# esp.net
KiCad netlist of a schematic drawn in EAGLE
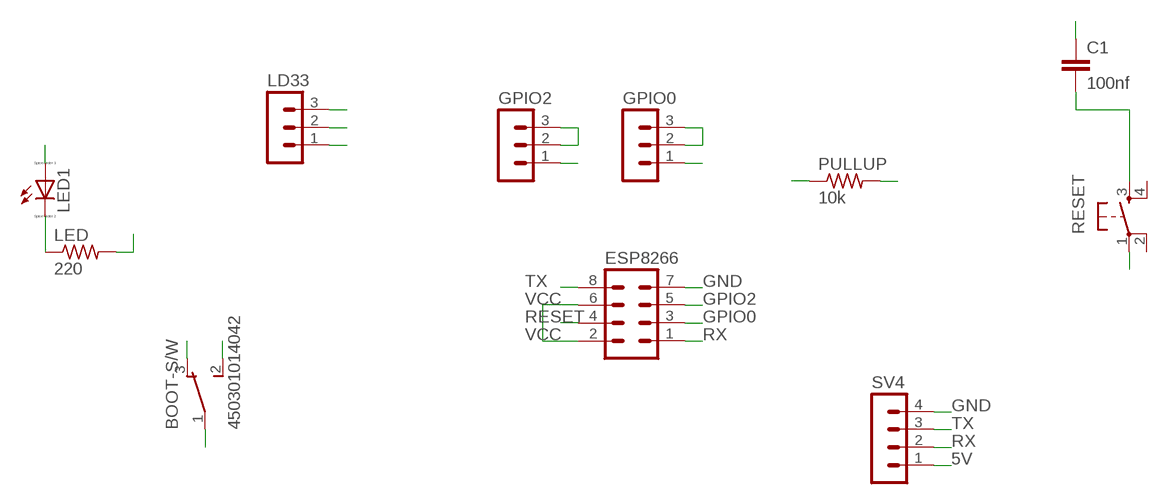
[diagram p0: schematic, sheet 1]

(export (version "E")
  (design (tool "Eeschema 10.0.6"))
  (components
    (comp (ref "BOOT-S/W")
      (value "450301014042")
      (footprint "eagle-import:450301014042")
      (libsource (lib "eagle-import") (part "450301014042"))
    )
    (comp (ref "C1")
      (value "100nf")
      (footprint "eagle-import:C025-024X044")
      (libsource (lib "eagle-import") (part "C-EU025-024X044"))
    )
    (comp (ref "ESP8266")
      (value "MA04-2")
      (footprint "eagle-import:MA04-2")
      (libsource (lib "eagle-import") (part "MA04-2"))
    )
    (comp (ref "GPIO0")
      (value "MA03-1")
      (footprint "eagle-import:MA03-1")
      (libsource (lib "eagle-import") (part "MA03-1"))
    )
    (comp (ref "GPIO2")
      (value "MA03-1")
      (footprint "eagle-import:MA03-1")
      (libsource (lib "eagle-import") (part "MA03-1"))
    )
    (comp (ref "LD33")
      (value "MA03-1")
      (footprint "eagle-import:MA03-1")
      (libsource (lib "eagle-import") (part "MA03-1"))
    )
    (comp (ref "LED")
      (value "220")
      (footprint "eagle-import:0204_5")
      (libsource (lib "eagle-import") (part "R-US_0204/5"))
    )
    (comp (ref "LED1")
      (value "LED_ELD260")
      (footprint "eagle-import:LED_LD260")
      (libsource (lib "eagle-import") (part "LED_ELD260"))
    )
    (comp (ref "PULLUP")
      (value "10k")
      (footprint "eagle-import:0204_5")
      (libsource (lib "eagle-import") (part "R-US_0204/5"))
    )
    (comp (ref "RESET")
      (value "DTS-6")
      (footprint "eagle-import:DTS-6")
      (libsource (lib "eagle-import") (part "DTS-6"))
    )
    (comp (ref "SV4")
      (value "MA04-1")
      (footprint "eagle-import:MA04-1")
      (libsource (lib "eagle-import") (part "MA04-1"))
    )
  )
  (nets
    (net (code "1") (name "/5V") (class "Default")
      (node (ref "LD33") (pin "1") (pinfunction "1_1") (pintype "passive"))
      (node (ref "SV4") (pin "1") (pinfunction "1_1") (pintype "passive"))
    )
    (net (code "2") (name "/GND") (class "Default")
      (node (ref "BOOT-S/W") (pin "3") (pinfunction "3_3") (pintype "passive"))
      (node (ref "ESP8266") (pin "7") (pinfunction "7_7") (pintype "passive"))
      (node (ref "GPIO0") (pin "1") (pinfunction "1_1") (pintype "passive"))
      (node (ref "GPIO2") (pin "1") (pinfunction "1_1") (pintype "passive"))
      (node (ref "LD33") (pin "2") (pinfunction "2_2") (pintype "passive"))
      (node (ref "LED") (pin "2") (pinfunction "2_2") (pintype "passive"))
      (node (ref "RESET") (pin "1") (pinfunction "1_1") (pintype "passive"))
      (node (ref "SV4") (pin "4") (pinfunction "4_4") (pintype "passive"))
    )
    (net (code "3") (name "/GPIO0") (class "Default")
      (node (ref "BOOT-S/W") (pin "1") (pinfunction "1_1") (pintype "passive"))
      (node (ref "ESP8266") (pin "3") (pinfunction "3_3") (pintype "passive"))
    )
    (net (code "4") (name "/GPIO0--") (class "Default")
      (node (ref "BOOT-S/W") (pin "2") (pinfunction "2_2") (pintype "passive"))
      (node (ref "GPIO0") (pin "2") (pinfunction "2_2") (pintype "passive"))
      (node (ref "GPIO0") (pin "3") (pinfunction "3_3") (pintype "passive"))
    )
    (net (code "5") (name "/GPIO2") (class "Default")
      (node (ref "ESP8266") (pin "5") (pinfunction "5_5") (pintype "passive"))
      (node (ref "GPIO2") (pin "2") (pinfunction "2_2") (pintype "passive"))
      (node (ref "GPIO2") (pin "3") (pinfunction "3_3") (pintype "passive"))
      (node (ref "LED1") (pin "A") (pinfunction "A_A") (pintype "passive"))
    )
    (net (code "6") (name "/RESET") (class "Default")
      (node (ref "C1") (pin "1") (pinfunction "1_1") (pintype "passive"))
      (node (ref "ESP8266") (pin "4") (pinfunction "4_4") (pintype "passive"))
      (node (ref "PULLUP") (pin "1") (pinfunction "1_1") (pintype "passive"))
    )
    (net (code "7") (name "/RX") (class "Default")
      (node (ref "ESP8266") (pin "1") (pinfunction "1_1") (pintype "passive"))
      (node (ref "SV4") (pin "2") (pinfunction "2_2") (pintype "passive"))
    )
    (net (code "8") (name "/TX") (class "Default")
      (node (ref "ESP8266") (pin "8") (pinfunction "8_8") (pintype "passive"))
      (node (ref "SV4") (pin "3") (pinfunction "3_3") (pintype "passive"))
    )
    (net (code "9") (name "/VCC") (class "Default")
      (node (ref "ESP8266") (pin "2") (pinfunction "2_2") (pintype "passive"))
      (node (ref "ESP8266") (pin "6") (pinfunction "6_6") (pintype "passive"))
      (node (ref "LD33") (pin "3") (pinfunction "3_3") (pintype "passive"))
      (node (ref "PULLUP") (pin "2") (pinfunction "2_2") (pintype "passive"))
    )
    (net (code "10") (name "Net-(C1-Pad2)") (class "Default")
      (node (ref "C1") (pin "2") (pinfunction "2_2") (pintype "passive"))
      (node (ref "RESET") (pin "3") (pinfunction "3_3") (pintype "passive"))
    )
    (net (code "11") (name "Net-(LED1-C)") (class "Default")
      (node (ref "LED") (pin "1") (pinfunction "1_1") (pintype "passive"))
      (node (ref "LED1") (pin "K") (pinfunction "C_K") (pintype "passive"))
    )
    (net (code "12") (name "unconnected-(RESET-Pad2)") (class "Default")
      (node (ref "RESET") (pin "2") (pinfunction "2_2") (pintype "passive"))
    )
    (net (code "13") (name "unconnected-(RESET-Pad4)") (class "Default")
      (node (ref "RESET") (pin "4") (pinfunction "4_4") (pintype "passive"))
    )
  )
)
